# INVERTER.net
KiCad netlist of a schematic drawn in Altium Designer
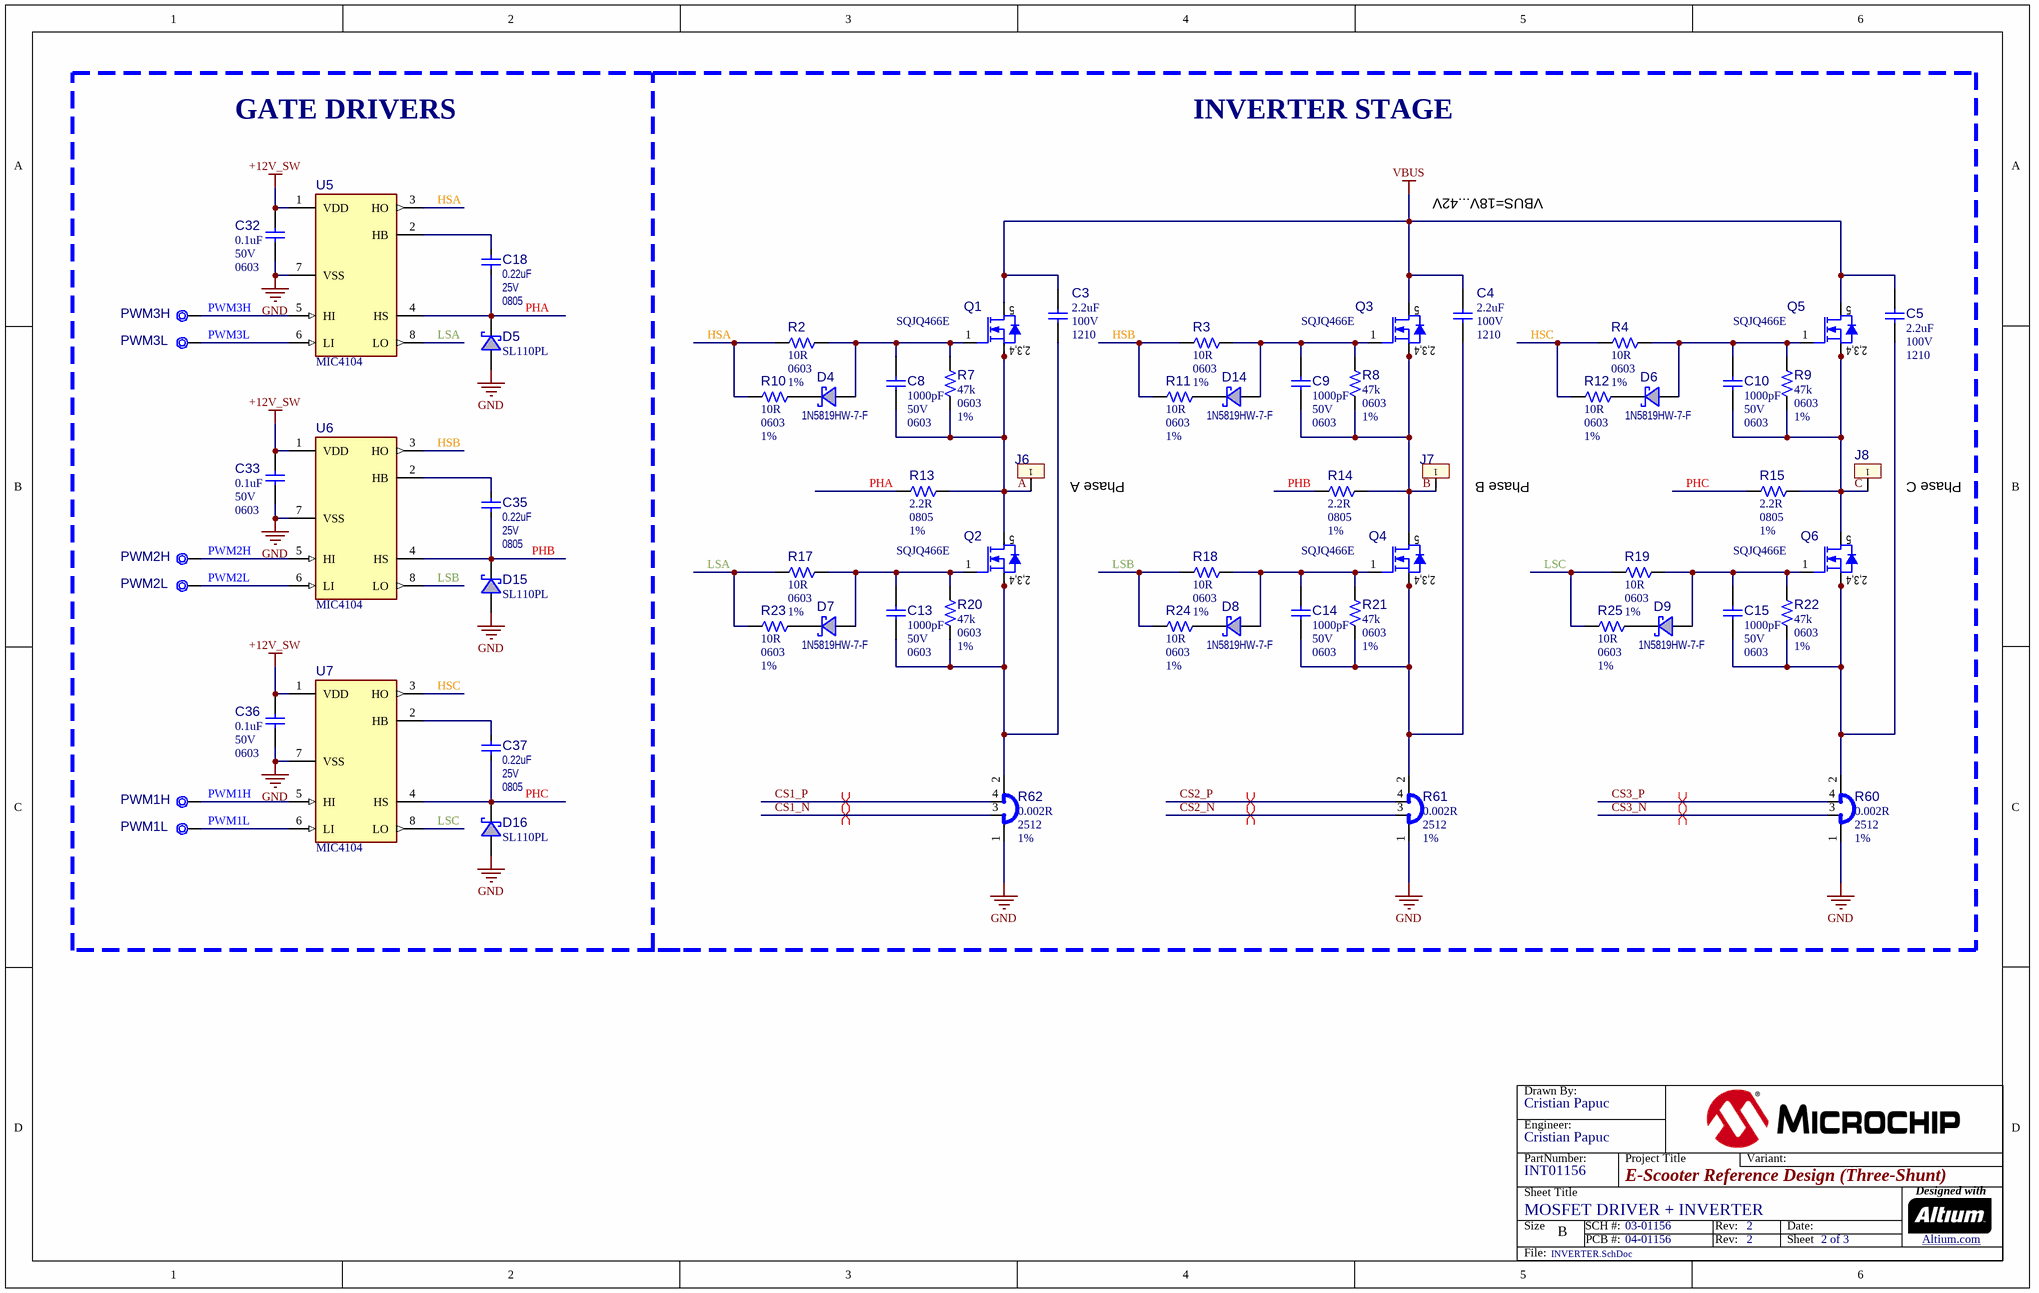
[diagram p0: INVERTER.SchDoc]

(export (version "E")
  (design (tool "Eeschema 10.0.6"))
  (components
    (comp (ref "C3")
      (value "2.2uF")
      (footprint "CAP_C_1210")
      (description "Capacitor")
      (fields
        (field (name "VOLTAGE") "100V")
        (field (name "PACKAGE") "1210")
        (field (name "TOLERANCE") "10%")
        (field (name "Comment") "Capacitor NP")
        (field (name "OWNER") "Mihai T(M91442)")
      )
      (libsource (lib "") (part "Capacitor NP_2"))
    )
    (comp (ref "C4")
      (value "2.2uF")
      (footprint "CAP_C_1210")
      (description "Capacitor")
      (fields
        (field (name "VOLTAGE") "100V")
        (field (name "PACKAGE") "1210")
        (field (name "TOLERANCE") "10%")
        (field (name "Comment") "Capacitor NP")
        (field (name "OWNER") "Mihai T(M91442)")
      )
      (libsource (lib "") (part "Capacitor NP_2"))
    )
    (comp (ref "C5")
      (value "2.2uF")
      (footprint "CAP_C_1210")
      (description "Capacitor")
      (fields
        (field (name "VOLTAGE") "100V")
        (field (name "PACKAGE") "1210")
        (field (name "TOLERANCE") "10%")
        (field (name "Comment") "Capacitor NP")
        (field (name "OWNER") "Mihai T(M91442)")
      )
      (libsource (lib "") (part "Capacitor NP_2"))
    )
    (comp (ref "C8")
      (value "1000pF")
      (footprint "CAP_C_0603")
      (fields
        (field (name "VOLTAGE") "50V")
        (field (name "PACKAGE") "0603")
        (field (name "TOLERANCE") "10%")
        (field (name "Comment") "Capacitor NP")
        (field (name "OWNER") "Gabor Bihari")
      )
      (libsource (lib "MCHP-CDB") (part "Capacitor NP"))
    )
    (comp (ref "C9")
      (value "1000pF")
      (footprint "CAP_C_0603")
      (fields
        (field (name "VOLTAGE") "50V")
        (field (name "PACKAGE") "0603")
        (field (name "TOLERANCE") "10%")
        (field (name "Comment") "Capacitor NP")
        (field (name "OWNER") "Gabor Bihari")
      )
      (libsource (lib "MCHP-CDB") (part "Capacitor NP"))
    )
    (comp (ref "C10")
      (value "1000pF")
      (footprint "CAP_C_0603")
      (fields
        (field (name "VOLTAGE") "50V")
        (field (name "PACKAGE") "0603")
        (field (name "TOLERANCE") "10%")
        (field (name "Comment") "Capacitor NP")
        (field (name "OWNER") "Gabor Bihari")
      )
      (libsource (lib "MCHP-CDB") (part "Capacitor NP"))
    )
    (comp (ref "C13")
      (value "1000pF")
      (footprint "CAP_C_0603")
      (fields
        (field (name "VOLTAGE") "50V")
        (field (name "PACKAGE") "0603")
        (field (name "TOLERANCE") "10%")
        (field (name "Comment") "Capacitor NP")
        (field (name "OWNER") "Gabor Bihari")
      )
      (libsource (lib "MCHP-CDB") (part "Capacitor NP"))
    )
    (comp (ref "C14")
      (value "1000pF")
      (footprint "CAP_C_0603")
      (fields
        (field (name "VOLTAGE") "50V")
        (field (name "PACKAGE") "0603")
        (field (name "TOLERANCE") "10%")
        (field (name "Comment") "Capacitor NP")
        (field (name "OWNER") "Gabor Bihari")
      )
      (libsource (lib "MCHP-CDB") (part "Capacitor NP"))
    )
    (comp (ref "C15")
      (value "1000pF")
      (footprint "CAP_C_0603")
      (fields
        (field (name "VOLTAGE") "50V")
        (field (name "PACKAGE") "0603")
        (field (name "TOLERANCE") "10%")
        (field (name "Comment") "Capacitor NP")
        (field (name "OWNER") "Gabor Bihari")
      )
      (libsource (lib "MCHP-CDB") (part "Capacitor NP"))
    )
    (comp (ref "C18")
      (value "0.22uF")
      (footprint "CAP_C_0805")
      (fields
        (field (name "VOLTAGE") "25V")
        (field (name "PACKAGE") "0805")
        (field (name "TOLERANCE") "10%")
        (field (name "Comment") "Capacitor NP")
      )
      (libsource (lib "") (part "Capacitor NP_1"))
    )
    (comp (ref "C32")
      (value "0.1uF")
      (footprint "CAP_C_0603")
      (description "Capacitor")
      (fields
        (field (name "VOLTAGE") "50V")
        (field (name "PACKAGE") "0603")
        (field (name "TOLERANCE") "10%")
        (field (name "Comment") "Capacitor NP")
        (field (name "OWNER") "Sam Charles")
      )
      (libsource (lib "MCHP-CDB") (part "Capacitor NP"))
    )
    (comp (ref "C33")
      (value "0.1uF")
      (footprint "CAP_C_0603")
      (description "Capacitor")
      (fields
        (field (name "VOLTAGE") "50V")
        (field (name "PACKAGE") "0603")
        (field (name "TOLERANCE") "10%")
        (field (name "Comment") "Capacitor NP")
        (field (name "OWNER") "Sam Charles")
      )
      (libsource (lib "MCHP-CDB") (part "Capacitor NP"))
    )
    (comp (ref "C35")
      (value "0.22uF")
      (footprint "CAP_C_0805")
      (fields
        (field (name "VOLTAGE") "25V")
        (field (name "PACKAGE") "0805")
        (field (name "TOLERANCE") "10%")
        (field (name "Comment") "Capacitor NP")
      )
      (libsource (lib "") (part "Capacitor NP_1"))
    )
    (comp (ref "C36")
      (value "0.1uF")
      (footprint "CAP_C_0603")
      (description "Capacitor")
      (fields
        (field (name "VOLTAGE") "50V")
        (field (name "PACKAGE") "0603")
        (field (name "TOLERANCE") "10%")
        (field (name "Comment") "Capacitor NP")
        (field (name "OWNER") "Sam Charles")
      )
      (libsource (lib "MCHP-CDB") (part "Capacitor NP"))
    )
    (comp (ref "C37")
      (value "0.22uF")
      (footprint "CAP_C_0805")
      (fields
        (field (name "VOLTAGE") "25V")
        (field (name "PACKAGE") "0805")
        (field (name "TOLERANCE") "10%")
        (field (name "Comment") "Capacitor NP")
      )
      (libsource (lib "") (part "Capacitor NP_1"))
    )
    (comp (ref "D4")
      (value "1N5819HW-7-F")
      (footprint "SOD-123")
      (description "DIO SCTKY RB160M-60TR 550mV 1A 60V SMD SOD-123F")
      (fields
        (field (name "POWER") "450mW")
        (field (name "Comment") "Diode Schottky")
        (field (name "OWNER") "Sorin Stanoaia")
      )
      (libsource (lib "MCHP-CDB") (part "Diode Schottky"))
    )
    (comp (ref "D5")
      (value "SL110PL")
      (footprint "SOD-123FL")
      (description "DIO SCTKY RB160M-60TR 550mV 1A 60V SMD SOD-123F")
      (fields (field (name "Comment") "Diode Schottky") (field (name "OWNER") "Tad Ahlvers"))
      (libsource (lib "MCHP-CDB") (part "Diode Schottky"))
    )
    (comp (ref "D6")
      (value "1N5819HW-7-F")
      (footprint "SOD-123")
      (description "DIO SCTKY RB160M-60TR 550mV 1A 60V SMD SOD-123F")
      (fields
        (field (name "POWER") "450mW")
        (field (name "Comment") "Diode Schottky")
        (field (name "OWNER") "Sorin Stanoaia")
      )
      (libsource (lib "MCHP-CDB") (part "Diode Schottky"))
    )
    (comp (ref "D7")
      (value "1N5819HW-7-F")
      (footprint "SOD-123")
      (description "DIO SCTKY RB160M-60TR 550mV 1A 60V SMD SOD-123F")
      (fields
        (field (name "POWER") "450mW")
        (field (name "Comment") "Diode Schottky")
        (field (name "OWNER") "Sorin Stanoaia")
      )
      (libsource (lib "MCHP-CDB") (part "Diode Schottky"))
    )
    (comp (ref "D8")
      (value "1N5819HW-7-F")
      (footprint "SOD-123")
      (description "DIO SCTKY RB160M-60TR 550mV 1A 60V SMD SOD-123F")
      (fields
        (field (name "POWER") "450mW")
        (field (name "Comment") "Diode Schottky")
        (field (name "OWNER") "Sorin Stanoaia")
      )
      (libsource (lib "MCHP-CDB") (part "Diode Schottky"))
    )
    (comp (ref "D9")
      (value "1N5819HW-7-F")
      (footprint "SOD-123")
      (description "DIO SCTKY RB160M-60TR 550mV 1A 60V SMD SOD-123F")
      (fields
        (field (name "POWER") "450mW")
        (field (name "Comment") "Diode Schottky")
        (field (name "OWNER") "Sorin Stanoaia")
      )
      (libsource (lib "MCHP-CDB") (part "Diode Schottky"))
    )
    (comp (ref "D14")
      (value "1N5819HW-7-F")
      (footprint "SOD-123")
      (description "DIO SCTKY RB160M-60TR 550mV 1A 60V SMD SOD-123F")
      (fields
        (field (name "POWER") "450mW")
        (field (name "Comment") "Diode Schottky")
        (field (name "OWNER") "Sorin Stanoaia")
      )
      (libsource (lib "MCHP-CDB") (part "Diode Schottky"))
    )
    (comp (ref "D15")
      (value "SL110PL")
      (footprint "SOD-123FL")
      (description "DIO SCTKY RB160M-60TR 550mV 1A 60V SMD SOD-123F")
      (fields (field (name "Comment") "Diode Schottky") (field (name "OWNER") "Tad Ahlvers"))
      (libsource (lib "MCHP-CDB") (part "Diode Schottky"))
    )
    (comp (ref "D16")
      (value "SL110PL")
      (footprint "SOD-123FL")
      (description "DIO SCTKY RB160M-60TR 550mV 1A 60V SMD SOD-123F")
      (fields (field (name "Comment") "Diode Schottky") (field (name "OWNER") "Tad Ahlvers"))
      (libsource (lib "MCHP-CDB") (part "Diode Schottky"))
    )
    (comp (ref "J6")
      (value "Header 1x1")
      (footprint "CON_M_1x1_5.08_QC_TAB_SPADE_0.250_V")
      (description "CON HDR-2.54 Male 1x1 Gold 5.97MH TH VERT")
      (fields (field (name "OWNER") "Octavian Stroe"))
      (libsource (lib "MCHP-CDB") (part "Header 1x1"))
    )
    (comp (ref "J7")
      (value "Header 1x1")
      (footprint "CON_M_1x1_5.08_QC_TAB_SPADE_0.250_V")
      (description "CON HDR-2.54 Male 1x1 Gold 5.97MH TH VERT")
      (fields (field (name "OWNER") "Octavian Stroe"))
      (libsource (lib "MCHP-CDB") (part "Header 1x1"))
    )
    (comp (ref "J8")
      (value "Header 1x1")
      (footprint "CON_M_1x1_5.08_QC_TAB_SPADE_0.250_V")
      (description "CON HDR-2.54 Male 1x1 Gold 5.97MH TH VERT")
      (fields (field (name "OWNER") "Octavian Stroe"))
      (libsource (lib "MCHP-CDB") (part "Header 1x1"))
    )
    (comp (ref "PWM1H")
      (value "Test Point No BOM")
      (footprint "TP_1.2x0.7")
      (description "Test Point")
      (fields (field (name "OWNER") "Bogdan P (M91398)"))
      (libsource (lib "MCHP-CDB") (part "Test Point No BOM"))
    )
    (comp (ref "PWM1L")
      (value "Test Point No BOM")
      (footprint "TP_1.2x0.7")
      (description "Test Point")
      (fields (field (name "OWNER") "Bogdan P (M91398)"))
      (libsource (lib "MCHP-CDB") (part "Test Point No BOM"))
    )
    (comp (ref "PWM2H")
      (value "Test Point No BOM")
      (footprint "TP_1.2x0.7")
      (description "Test Point")
      (fields (field (name "OWNER") "Bogdan P (M91398)"))
      (libsource (lib "MCHP-CDB") (part "Test Point No BOM"))
    )
    (comp (ref "PWM2L")
      (value "Test Point No BOM")
      (footprint "TP_1.2x0.7")
      (description "Test Point")
      (fields (field (name "OWNER") "Bogdan P (M91398)"))
      (libsource (lib "MCHP-CDB") (part "Test Point No BOM"))
    )
    (comp (ref "PWM3H")
      (value "Test Point No BOM")
      (footprint "TP_1.2x0.7")
      (description "Test Point")
      (fields (field (name "OWNER") "Bogdan P (M91398)"))
      (libsource (lib "MCHP-CDB") (part "Test Point No BOM"))
    )
    (comp (ref "PWM3L")
      (value "Test Point No BOM")
      (footprint "TP_1.2x0.7")
      (description "Test Point")
      (fields (field (name "OWNER") "Bogdan P (M91398)"))
      (libsource (lib "MCHP-CDB") (part "Test Point No BOM"))
    )
    (comp (ref "Q1")
      (value "SQJQ466E")
      (footprint "PPAK_SO-8L_8x8_ALTERNATE")
      (description "Transistor MOS")
      (fields
        (field (name "POWER") "150W")
        (field (name "VOLTAGE") "60V")
        (field (name "OWNER") "Octavian Stroe")
      )
      (libsource (lib "MCHP-CDB") (part "Transistor MOS-N GSSSD"))
    )
    (comp (ref "Q2")
      (value "SQJQ466E")
      (footprint "PPAK_SO-8L_8x8_ALTERNATE")
      (description "Transistor MOS")
      (fields
        (field (name "POWER") "150W")
        (field (name "VOLTAGE") "60V")
        (field (name "OWNER") "Octavian Stroe")
      )
      (libsource (lib "MCHP-CDB") (part "Transistor MOS-N GSSSD"))
    )
    (comp (ref "Q3")
      (value "SQJQ466E")
      (footprint "PPAK_SO-8L_8x8_ALTERNATE")
      (description "Transistor MOS")
      (fields
        (field (name "POWER") "150W")
        (field (name "VOLTAGE") "60V")
        (field (name "OWNER") "Octavian Stroe")
      )
      (libsource (lib "MCHP-CDB") (part "Transistor MOS-N GSSSD"))
    )
    (comp (ref "Q4")
      (value "SQJQ466E")
      (footprint "PPAK_SO-8L_8x8_ALTERNATE")
      (description "Transistor MOS")
      (fields
        (field (name "POWER") "150W")
        (field (name "VOLTAGE") "60V")
        (field (name "OWNER") "Octavian Stroe")
      )
      (libsource (lib "MCHP-CDB") (part "Transistor MOS-N GSSSD"))
    )
    (comp (ref "Q5")
      (value "SQJQ466E")
      (footprint "PPAK_SO-8L_8x8_ALTERNATE")
      (description "Transistor MOS")
      (fields
        (field (name "POWER") "150W")
        (field (name "VOLTAGE") "60V")
        (field (name "OWNER") "Octavian Stroe")
      )
      (libsource (lib "MCHP-CDB") (part "Transistor MOS-N GSSSD"))
    )
    (comp (ref "Q6")
      (value "SQJQ466E")
      (footprint "PPAK_SO-8L_8x8_ALTERNATE")
      (description "Transistor MOS")
      (fields
        (field (name "POWER") "150W")
        (field (name "VOLTAGE") "60V")
        (field (name "OWNER") "Octavian Stroe")
      )
      (libsource (lib "MCHP-CDB") (part "Transistor MOS-N GSSSD"))
    )
    (comp (ref "R2")
      (value "10R")
      (footprint "RES_C_0603")
      (description "Resistor")
      (fields
        (field (name "PACKAGE") "0603")
        (field (name "TOLERANCE") "1%")
        (field (name "VOLTAGE") "75V")
        (field (name "POWER") "1/10W")
      )
      (libsource (lib "MCHP-CDB") (part "Resistor"))
    )
    (comp (ref "R3")
      (value "10R")
      (footprint "RES_C_0603")
      (description "Resistor")
      (fields
        (field (name "PACKAGE") "0603")
        (field (name "TOLERANCE") "1%")
        (field (name "VOLTAGE") "75V")
        (field (name "POWER") "1/10W")
      )
      (libsource (lib "MCHP-CDB") (part "Resistor"))
    )
    (comp (ref "R4")
      (value "10R")
      (footprint "RES_C_0603")
      (description "Resistor")
      (fields
        (field (name "PACKAGE") "0603")
        (field (name "TOLERANCE") "1%")
        (field (name "VOLTAGE") "75V")
        (field (name "POWER") "1/10W")
      )
      (libsource (lib "MCHP-CDB") (part "Resistor"))
    )
    (comp (ref "R7")
      (value "47k")
      (footprint "RES_C_0603")
      (description "Resistor")
      (fields
        (field (name "PACKAGE") "0603")
        (field (name "TOLERANCE") "1%")
        (field (name "VOLTAGE") "75V")
        (field (name "POWER") "1/10W")
        (field (name "OWNER") "Adrian M (M91404)")
      )
      (libsource (lib "MCHP-CDB") (part "Resistor"))
    )
    (comp (ref "R8")
      (value "47k")
      (footprint "RES_C_0603")
      (description "Resistor")
      (fields
        (field (name "PACKAGE") "0603")
        (field (name "TOLERANCE") "1%")
        (field (name "VOLTAGE") "75V")
        (field (name "POWER") "1/10W")
        (field (name "OWNER") "Adrian M (M91404)")
      )
      (libsource (lib "MCHP-CDB") (part "Resistor"))
    )
    (comp (ref "R9")
      (value "47k")
      (footprint "RES_C_0603")
      (description "Resistor")
      (fields
        (field (name "PACKAGE") "0603")
        (field (name "TOLERANCE") "1%")
        (field (name "VOLTAGE") "75V")
        (field (name "POWER") "1/10W")
        (field (name "OWNER") "Adrian M (M91404)")
      )
      (libsource (lib "MCHP-CDB") (part "Resistor"))
    )
    (comp (ref "R10")
      (value "10R")
      (footprint "RES_C_0603")
      (description "Resistor")
      (fields
        (field (name "PACKAGE") "0603")
        (field (name "TOLERANCE") "1%")
        (field (name "VOLTAGE") "75V")
        (field (name "POWER") "1/10W")
      )
      (libsource (lib "MCHP-CDB") (part "Resistor"))
    )
    (comp (ref "R11")
      (value "10R")
      (footprint "RES_C_0603")
      (description "Resistor")
      (fields
        (field (name "PACKAGE") "0603")
        (field (name "TOLERANCE") "1%")
        (field (name "VOLTAGE") "75V")
        (field (name "POWER") "1/10W")
      )
      (libsource (lib "MCHP-CDB") (part "Resistor"))
    )
    (comp (ref "R12")
      (value "10R")
      (footprint "RES_C_0603")
      (description "Resistor")
      (fields
        (field (name "PACKAGE") "0603")
        (field (name "TOLERANCE") "1%")
        (field (name "VOLTAGE") "75V")
        (field (name "POWER") "1/10W")
      )
      (libsource (lib "MCHP-CDB") (part "Resistor"))
    )
    (comp (ref "R13")
      (value "2.2R")
      (footprint "RES_C_0805")
      (description "Resistor")
      (fields
        (field (name "PACKAGE") "0805")
        (field (name "TOLERANCE") "1%")
        (field (name "VOLTAGE") "150V")
        (field (name "POWER") "1/8W")
        (field (name "OWNER") "Cristian Papuc")
      )
      (libsource (lib "MCHP-CDB") (part "Resistor"))
    )
    (comp (ref "R14")
      (value "2.2R")
      (footprint "RES_C_0805")
      (description "Resistor")
      (fields
        (field (name "PACKAGE") "0805")
        (field (name "TOLERANCE") "1%")
        (field (name "VOLTAGE") "150V")
        (field (name "POWER") "1/8W")
        (field (name "OWNER") "Cristian Papuc")
      )
      (libsource (lib "MCHP-CDB") (part "Resistor"))
    )
    (comp (ref "R15")
      (value "2.2R")
      (footprint "RES_C_0805")
      (description "Resistor")
      (fields
        (field (name "PACKAGE") "0805")
        (field (name "TOLERANCE") "1%")
        (field (name "VOLTAGE") "150V")
        (field (name "POWER") "1/8W")
        (field (name "OWNER") "Cristian Papuc")
      )
      (libsource (lib "MCHP-CDB") (part "Resistor"))
    )
    (comp (ref "R17")
      (value "10R")
      (footprint "RES_C_0603")
      (description "Resistor")
      (fields
        (field (name "PACKAGE") "0603")
        (field (name "TOLERANCE") "1%")
        (field (name "VOLTAGE") "75V")
        (field (name "POWER") "1/10W")
      )
      (libsource (lib "MCHP-CDB") (part "Resistor"))
    )
    (comp (ref "R18")
      (value "10R")
      (footprint "RES_C_0603")
      (description "Resistor")
      (fields
        (field (name "PACKAGE") "0603")
        (field (name "TOLERANCE") "1%")
        (field (name "VOLTAGE") "75V")
        (field (name "POWER") "1/10W")
      )
      (libsource (lib "MCHP-CDB") (part "Resistor"))
    )
    (comp (ref "R19")
      (value "10R")
      (footprint "RES_C_0603")
      (description "Resistor")
      (fields
        (field (name "PACKAGE") "0603")
        (field (name "TOLERANCE") "1%")
        (field (name "VOLTAGE") "75V")
        (field (name "POWER") "1/10W")
      )
      (libsource (lib "MCHP-CDB") (part "Resistor"))
    )
    (comp (ref "R20")
      (value "47k")
      (footprint "RES_C_0603")
      (description "Resistor")
      (fields
        (field (name "PACKAGE") "0603")
        (field (name "TOLERANCE") "1%")
        (field (name "VOLTAGE") "75V")
        (field (name "POWER") "1/10W")
        (field (name "OWNER") "Adrian M (M91404)")
      )
      (libsource (lib "MCHP-CDB") (part "Resistor"))
    )
    (comp (ref "R21")
      (value "47k")
      (footprint "RES_C_0603")
      (description "Resistor")
      (fields
        (field (name "PACKAGE") "0603")
        (field (name "TOLERANCE") "1%")
        (field (name "VOLTAGE") "75V")
        (field (name "POWER") "1/10W")
        (field (name "OWNER") "Adrian M (M91404)")
      )
      (libsource (lib "MCHP-CDB") (part "Resistor"))
    )
    (comp (ref "R22")
      (value "47k")
      (footprint "RES_C_0603")
      (description "Resistor")
      (fields
        (field (name "PACKAGE") "0603")
        (field (name "TOLERANCE") "1%")
        (field (name "VOLTAGE") "75V")
        (field (name "POWER") "1/10W")
        (field (name "OWNER") "Adrian M (M91404)")
      )
      (libsource (lib "MCHP-CDB") (part "Resistor"))
    )
    (comp (ref "R23")
      (value "10R")
      (footprint "RES_C_0603")
      (description "Resistor")
      (fields
        (field (name "PACKAGE") "0603")
        (field (name "TOLERANCE") "1%")
        (field (name "VOLTAGE") "75V")
        (field (name "POWER") "1/10W")
      )
      (libsource (lib "MCHP-CDB") (part "Resistor"))
    )
    (comp (ref "R24")
      (value "10R")
      (footprint "RES_C_0603")
      (description "Resistor")
      (fields
        (field (name "PACKAGE") "0603")
        (field (name "TOLERANCE") "1%")
        (field (name "VOLTAGE") "75V")
        (field (name "POWER") "1/10W")
      )
      (libsource (lib "MCHP-CDB") (part "Resistor"))
    )
    (comp (ref "R25")
      (value "10R")
      (footprint "RES_C_0603")
      (description "Resistor")
      (fields
        (field (name "PACKAGE") "0603")
        (field (name "TOLERANCE") "1%")
        (field (name "VOLTAGE") "75V")
        (field (name "POWER") "1/10W")
      )
      (libsource (lib "MCHP-CDB") (part "Resistor"))
    )
    (comp (ref "R60")
      (value "0.002R")
      (footprint "RES_C_2512_SHUNT_Metal")
      (description "Shunt")
      (fields
        (field (name "PACKAGE") "2512")
        (field (name "TOLERANCE") "1%")
        (field (name "POWER") "5W")
        (field (name "Comment") "Shunt 4 Pin")
        (field (name "OWNER") "Octavian Stroe")
      )
      (libsource (lib "MCHP-CDB") (part "Shunt 4 Pin"))
    )
    (comp (ref "R61")
      (value "0.002R")
      (footprint "RES_C_2512_SHUNT_Metal")
      (description "Shunt")
      (fields
        (field (name "PACKAGE") "2512")
        (field (name "TOLERANCE") "1%")
        (field (name "POWER") "5W")
        (field (name "Comment") "Shunt 4 Pin")
        (field (name "OWNER") "Octavian Stroe")
      )
      (libsource (lib "MCHP-CDB") (part "Shunt 4 Pin"))
    )
    (comp (ref "R62")
      (value "0.002R")
      (footprint "RES_C_2512_SHUNT_Metal")
      (description "Shunt")
      (fields
        (field (name "PACKAGE") "2512")
        (field (name "TOLERANCE") "1%")
        (field (name "POWER") "5W")
        (field (name "Comment") "Shunt 4 Pin")
        (field (name "OWNER") "Octavian Stroe")
      )
      (libsource (lib "MCHP-CDB") (part "Shunt 4 Pin"))
    )
    (comp (ref "U5")
      (value "MIC4104")
      (footprint "SOIC-8")
      (description "MOSFET DRIVER")
      (fields (field (name "Comment") "MIC4104 SOIC-8") (field (name "OWNER") "Ed Kennedy"))
      (libsource (lib "MCHP-CDB") (part "MIC4104 SOIC-8"))
    )
    (comp (ref "U6")
      (value "MIC4104")
      (footprint "SOIC-8")
      (description "MOSFET DRIVER")
      (fields (field (name "Comment") "MIC4104 SOIC-8") (field (name "OWNER") "Ed Kennedy"))
      (libsource (lib "MCHP-CDB") (part "MIC4104 SOIC-8"))
    )
    (comp (ref "U7")
      (value "MIC4104")
      (footprint "SOIC-8")
      (description "MOSFET DRIVER")
      (fields (field (name "Comment") "MIC4104 SOIC-8") (field (name "OWNER") "Ed Kennedy"))
      (libsource (lib "MCHP-CDB") (part "MIC4104 SOIC-8"))
    )
  )
  (nets
    (net (code "1") (name "+12V_SW") (class "Default")
      (node (ref "C32") (pin "2") (pinfunction "2_2") (pintype "passive"))
      (node (ref "C33") (pin "2") (pinfunction "2_2") (pintype "passive"))
      (node (ref "C36") (pin "2") (pinfunction "2_2") (pintype "passive"))
      (node (ref "U5") (pin "1") (pinfunction "VDD_1") (pintype "power_in"))
      (node (ref "U6") (pin "1") (pinfunction "VDD_1") (pintype "power_in"))
      (node (ref "U7") (pin "1") (pinfunction "VDD_1") (pintype "power_in"))
    )
    (net (code "2") (name "/A") (class "Default")
      (node (ref "C8") (pin "1") (pinfunction "1_1") (pintype "passive"))
      (node (ref "J6") (pin "1") (pinfunction "1_1") (pintype "passive"))
      (node (ref "Q1") (pin "2") (pinfunction "S_2") (pintype "passive"))
      (node (ref "Q1") (pin "3") (pinfunction "S_3") (pintype "passive"))
      (node (ref "Q1") (pin "4") (pinfunction "S_4") (pintype "passive"))
      (node (ref "Q2") (pin "5") (pinfunction "D_5") (pintype "passive"))
      (node (ref "R13") (pin "2") (pinfunction "2_2") (pintype "passive"))
      (node (ref "R7") (pin "1") (pinfunction "1_1") (pintype "passive"))
    )
    (net (code "3") (name "/B") (class "Default")
      (node (ref "C9") (pin "1") (pinfunction "1_1") (pintype "passive"))
      (node (ref "J7") (pin "1") (pinfunction "1_1") (pintype "passive"))
      (node (ref "Q3") (pin "2") (pinfunction "S_2") (pintype "passive"))
      (node (ref "Q3") (pin "3") (pinfunction "S_3") (pintype "passive"))
      (node (ref "Q3") (pin "4") (pinfunction "S_4") (pintype "passive"))
      (node (ref "Q4") (pin "5") (pinfunction "D_5") (pintype "passive"))
      (node (ref "R14") (pin "2") (pinfunction "2_2") (pintype "passive"))
      (node (ref "R8") (pin "1") (pinfunction "1_1") (pintype "passive"))
    )
    (net (code "4") (name "/C") (class "Default")
      (node (ref "C10") (pin "1") (pinfunction "1_1") (pintype "passive"))
      (node (ref "J8") (pin "1") (pinfunction "1_1") (pintype "passive"))
      (node (ref "Q5") (pin "2") (pinfunction "S_2") (pintype "passive"))
      (node (ref "Q5") (pin "3") (pinfunction "S_3") (pintype "passive"))
      (node (ref "Q5") (pin "4") (pinfunction "S_4") (pintype "passive"))
      (node (ref "Q6") (pin "5") (pinfunction "D_5") (pintype "passive"))
      (node (ref "R15") (pin "2") (pinfunction "2_2") (pintype "passive"))
      (node (ref "R9") (pin "1") (pinfunction "1_1") (pintype "passive"))
    )
    (net (code "5") (name "/CS1_N") (class "Default")
      (node (ref "R62") (pin "3") (pinfunction "3_3") (pintype "passive"))
    )
    (net (code "6") (name "/CS1_P") (class "Default")
      (node (ref "R62") (pin "4") (pinfunction "4_4") (pintype "passive"))
    )
    (net (code "7") (name "/CS2_N") (class "Default")
      (node (ref "R61") (pin "3") (pinfunction "3_3") (pintype "passive"))
    )
    (net (code "8") (name "/CS2_P") (class "Default")
      (node (ref "R61") (pin "4") (pinfunction "4_4") (pintype "passive"))
    )
    (net (code "9") (name "/CS3_N") (class "Default")
      (node (ref "R60") (pin "3") (pinfunction "3_3") (pintype "passive"))
    )
    (net (code "10") (name "/CS3_P") (class "Default")
      (node (ref "R60") (pin "4") (pinfunction "4_4") (pintype "passive"))
    )
    (net (code "11") (name "/HSA") (class "Default")
      (node (ref "R10") (pin "1") (pinfunction "1_1") (pintype "passive"))
      (node (ref "R2") (pin "1") (pinfunction "1_1") (pintype "passive"))
      (node (ref "U5") (pin "3") (pinfunction "HO_3") (pintype "output"))
    )
    (net (code "12") (name "/HSB") (class "Default")
      (node (ref "R11") (pin "1") (pinfunction "1_1") (pintype "passive"))
      (node (ref "R3") (pin "1") (pinfunction "1_1") (pintype "passive"))
      (node (ref "U6") (pin "3") (pinfunction "HO_3") (pintype "output"))
    )
    (net (code "13") (name "/HSC") (class "Default")
      (node (ref "R12") (pin "1") (pinfunction "1_1") (pintype "passive"))
      (node (ref "R4") (pin "1") (pinfunction "1_1") (pintype "passive"))
      (node (ref "U7") (pin "3") (pinfunction "HO_3") (pintype "output"))
    )
    (net (code "14") (name "/LSA") (class "Default")
      (node (ref "R17") (pin "1") (pinfunction "1_1") (pintype "passive"))
      (node (ref "R23") (pin "1") (pinfunction "1_1") (pintype "passive"))
      (node (ref "U5") (pin "8") (pinfunction "LO_8") (pintype "output"))
    )
    (net (code "15") (name "/LSB") (class "Default")
      (node (ref "R18") (pin "1") (pinfunction "1_1") (pintype "passive"))
      (node (ref "R24") (pin "1") (pinfunction "1_1") (pintype "passive"))
      (node (ref "U6") (pin "8") (pinfunction "LO_8") (pintype "output"))
    )
    (net (code "16") (name "/LSC") (class "Default")
      (node (ref "R19") (pin "1") (pinfunction "1_1") (pintype "passive"))
      (node (ref "R25") (pin "1") (pinfunction "1_1") (pintype "passive"))
      (node (ref "U7") (pin "8") (pinfunction "LO_8") (pintype "output"))
    )
    (net (code "17") (name "/PHA") (class "Default")
      (node (ref "C18") (pin "1") (pinfunction "1_1") (pintype "passive"))
      (node (ref "D5") (pin "2") (pinfunction "K_2") (pintype "passive"))
      (node (ref "R13") (pin "1") (pinfunction "1_1") (pintype "passive"))
      (node (ref "U5") (pin "4") (pinfunction "HS_4") (pintype "passive"))
    )
    (net (code "18") (name "/PHB") (class "Default")
      (node (ref "C35") (pin "1") (pinfunction "1_1") (pintype "passive"))
      (node (ref "D15") (pin "2") (pinfunction "K_2") (pintype "passive"))
      (node (ref "R14") (pin "1") (pinfunction "1_1") (pintype "passive"))
      (node (ref "U6") (pin "4") (pinfunction "HS_4") (pintype "passive"))
    )
    (net (code "19") (name "/PHC") (class "Default")
      (node (ref "C37") (pin "1") (pinfunction "1_1") (pintype "passive"))
      (node (ref "D16") (pin "2") (pinfunction "K_2") (pintype "passive"))
      (node (ref "R15") (pin "1") (pinfunction "1_1") (pintype "passive"))
      (node (ref "U7") (pin "4") (pinfunction "HS_4") (pintype "passive"))
    )
    (net (code "20") (name "/PWM1H") (class "Default")
      (node (ref "PWM1H") (pin "1") (pinfunction "1_1") (pintype "passive"))
      (node (ref "U7") (pin "5") (pinfunction "HI_5") (pintype "input"))
    )
    (net (code "21") (name "/PWM1L") (class "Default")
      (node (ref "PWM1L") (pin "1") (pinfunction "1_1") (pintype "passive"))
      (node (ref "U7") (pin "6") (pinfunction "LI_6") (pintype "input"))
    )
    (net (code "22") (name "/PWM2H") (class "Default")
      (node (ref "PWM2H") (pin "1") (pinfunction "1_1") (pintype "passive"))
      (node (ref "U6") (pin "5") (pinfunction "HI_5") (pintype "input"))
    )
    (net (code "23") (name "/PWM2L") (class "Default")
      (node (ref "PWM2L") (pin "1") (pinfunction "1_1") (pintype "passive"))
      (node (ref "U6") (pin "6") (pinfunction "LI_6") (pintype "input"))
    )
    (net (code "24") (name "/PWM3H") (class "Default")
      (node (ref "PWM3H") (pin "1") (pinfunction "1_1") (pintype "passive"))
      (node (ref "U5") (pin "5") (pinfunction "HI_5") (pintype "input"))
    )
    (net (code "25") (name "/PWM3L") (class "Default")
      (node (ref "PWM3L") (pin "1") (pinfunction "1_1") (pintype "passive"))
      (node (ref "U5") (pin "6") (pinfunction "LI_6") (pintype "input"))
    )
    (net (code "26") (name "GND") (class "Default")
      (node (ref "C32") (pin "1") (pinfunction "1_1") (pintype "passive"))
      (node (ref "C33") (pin "1") (pinfunction "1_1") (pintype "passive"))
      (node (ref "C36") (pin "1") (pinfunction "1_1") (pintype "passive"))
      (node (ref "D15") (pin "1") (pinfunction "A_1") (pintype "passive"))
      (node (ref "D16") (pin "1") (pinfunction "A_1") (pintype "passive"))
      (node (ref "D5") (pin "1") (pinfunction "A_1") (pintype "passive"))
      (node (ref "R60") (pin "1") (pinfunction "1_1") (pintype "passive"))
      (node (ref "R61") (pin "1") (pinfunction "1_1") (pintype "passive"))
      (node (ref "R62") (pin "1") (pinfunction "1_1") (pintype "passive"))
      (node (ref "U5") (pin "7") (pinfunction "VSS_7") (pintype "power_in"))
      (node (ref "U6") (pin "7") (pinfunction "VSS_7") (pintype "power_in"))
      (node (ref "U7") (pin "7") (pinfunction "VSS_7") (pintype "power_in"))
    )
    (net (code "27") (name "Net-(C13-Pad1)") (class "Default")
      (node (ref "C13") (pin "1") (pinfunction "1_1") (pintype "passive"))
      (node (ref "C3") (pin "1") (pinfunction "1_1") (pintype "passive"))
      (node (ref "Q2") (pin "2") (pinfunction "S_2") (pintype "passive"))
      (node (ref "Q2") (pin "3") (pinfunction "S_3") (pintype "passive"))
      (node (ref "Q2") (pin "4") (pinfunction "S_4") (pintype "passive"))
      (node (ref "R20") (pin "1") (pinfunction "1_1") (pintype "passive"))
      (node (ref "R62") (pin "2") (pinfunction "2_2") (pintype "passive"))
    )
    (net (code "28") (name "Net-(C14-Pad1)") (class "Default")
      (node (ref "C14") (pin "1") (pinfunction "1_1") (pintype "passive"))
      (node (ref "C4") (pin "1") (pinfunction "1_1") (pintype "passive"))
      (node (ref "Q4") (pin "2") (pinfunction "S_2") (pintype "passive"))
      (node (ref "Q4") (pin "3") (pinfunction "S_3") (pintype "passive"))
      (node (ref "Q4") (pin "4") (pinfunction "S_4") (pintype "passive"))
      (node (ref "R21") (pin "1") (pinfunction "1_1") (pintype "passive"))
      (node (ref "R61") (pin "2") (pinfunction "2_2") (pintype "passive"))
    )
    (net (code "29") (name "Net-(C15-Pad1)") (class "Default")
      (node (ref "C15") (pin "1") (pinfunction "1_1") (pintype "passive"))
      (node (ref "C5") (pin "1") (pinfunction "1_1") (pintype "passive"))
      (node (ref "Q6") (pin "2") (pinfunction "S_2") (pintype "passive"))
      (node (ref "Q6") (pin "3") (pinfunction "S_3") (pintype "passive"))
      (node (ref "Q6") (pin "4") (pinfunction "S_4") (pintype "passive"))
      (node (ref "R22") (pin "1") (pinfunction "1_1") (pintype "passive"))
      (node (ref "R60") (pin "2") (pinfunction "2_2") (pintype "passive"))
    )
    (net (code "30") (name "Net-(D4-A)") (class "Default")
      (node (ref "C8") (pin "2") (pinfunction "2_2") (pintype "passive"))
      (node (ref "D4") (pin "1") (pinfunction "A_1") (pintype "passive"))
      (node (ref "Q1") (pin "1") (pinfunction "G_1") (pintype "passive"))
      (node (ref "R2") (pin "2") (pinfunction "2_2") (pintype "passive"))
      (node (ref "R7") (pin "2") (pinfunction "2_2") (pintype "passive"))
    )
    (net (code "31") (name "Net-(D4-K)") (class "Default")
      (node (ref "D4") (pin "2") (pinfunction "K_2") (pintype "passive"))
      (node (ref "R10") (pin "2") (pinfunction "2_2") (pintype "passive"))
    )
    (net (code "32") (name "Net-(D6-A)") (class "Default")
      (node (ref "C10") (pin "2") (pinfunction "2_2") (pintype "passive"))
      (node (ref "D6") (pin "1") (pinfunction "A_1") (pintype "passive"))
      (node (ref "Q5") (pin "1") (pinfunction "G_1") (pintype "passive"))
      (node (ref "R4") (pin "2") (pinfunction "2_2") (pintype "passive"))
      (node (ref "R9") (pin "2") (pinfunction "2_2") (pintype "passive"))
    )
    (net (code "33") (name "Net-(D6-K)") (class "Default")
      (node (ref "D6") (pin "2") (pinfunction "K_2") (pintype "passive"))
      (node (ref "R12") (pin "2") (pinfunction "2_2") (pintype "passive"))
    )
    (net (code "34") (name "Net-(D7-A)") (class "Default")
      (node (ref "C13") (pin "2") (pinfunction "2_2") (pintype "passive"))
      (node (ref "D7") (pin "1") (pinfunction "A_1") (pintype "passive"))
      (node (ref "Q2") (pin "1") (pinfunction "G_1") (pintype "passive"))
      (node (ref "R17") (pin "2") (pinfunction "2_2") (pintype "passive"))
      (node (ref "R20") (pin "2") (pinfunction "2_2") (pintype "passive"))
    )
    (net (code "35") (name "Net-(D7-K)") (class "Default")
      (node (ref "D7") (pin "2") (pinfunction "K_2") (pintype "passive"))
      (node (ref "R23") (pin "2") (pinfunction "2_2") (pintype "passive"))
    )
    (net (code "36") (name "Net-(D8-A)") (class "Default")
      (node (ref "C14") (pin "2") (pinfunction "2_2") (pintype "passive"))
      (node (ref "D8") (pin "1") (pinfunction "A_1") (pintype "passive"))
      (node (ref "Q4") (pin "1") (pinfunction "G_1") (pintype "passive"))
      (node (ref "R18") (pin "2") (pinfunction "2_2") (pintype "passive"))
      (node (ref "R21") (pin "2") (pinfunction "2_2") (pintype "passive"))
    )
    (net (code "37") (name "Net-(D8-K)") (class "Default")
      (node (ref "D8") (pin "2") (pinfunction "K_2") (pintype "passive"))
      (node (ref "R24") (pin "2") (pinfunction "2_2") (pintype "passive"))
    )
    (net (code "38") (name "Net-(D9-A)") (class "Default")
      (node (ref "C15") (pin "2") (pinfunction "2_2") (pintype "passive"))
      (node (ref "D9") (pin "1") (pinfunction "A_1") (pintype "passive"))
      (node (ref "Q6") (pin "1") (pinfunction "G_1") (pintype "passive"))
      (node (ref "R19") (pin "2") (pinfunction "2_2") (pintype "passive"))
      (node (ref "R22") (pin "2") (pinfunction "2_2") (pintype "passive"))
    )
    (net (code "39") (name "Net-(D9-K)") (class "Default")
      (node (ref "D9") (pin "2") (pinfunction "K_2") (pintype "passive"))
      (node (ref "R25") (pin "2") (pinfunction "2_2") (pintype "passive"))
    )
    (net (code "40") (name "Net-(D14-A)") (class "Default")
      (node (ref "C9") (pin "2") (pinfunction "2_2") (pintype "passive"))
      (node (ref "D14") (pin "1") (pinfunction "A_1") (pintype "passive"))
      (node (ref "Q3") (pin "1") (pinfunction "G_1") (pintype "passive"))
      (node (ref "R3") (pin "2") (pinfunction "2_2") (pintype "passive"))
      (node (ref "R8") (pin "2") (pinfunction "2_2") (pintype "passive"))
    )
    (net (code "41") (name "Net-(D14-K)") (class "Default")
      (node (ref "D14") (pin "2") (pinfunction "K_2") (pintype "passive"))
      (node (ref "R11") (pin "2") (pinfunction "2_2") (pintype "passive"))
    )
    (net (code "42") (name "Net-(U5-HB)") (class "Default")
      (node (ref "C18") (pin "2") (pinfunction "2_2") (pintype "passive"))
      (node (ref "U5") (pin "2") (pinfunction "HB_2") (pintype "passive"))
    )
    (net (code "43") (name "Net-(U6-HB)") (class "Default")
      (node (ref "C35") (pin "2") (pinfunction "2_2") (pintype "passive"))
      (node (ref "U6") (pin "2") (pinfunction "HB_2") (pintype "passive"))
    )
    (net (code "44") (name "Net-(U7-HB)") (class "Default")
      (node (ref "C37") (pin "2") (pinfunction "2_2") (pintype "passive"))
      (node (ref "U7") (pin "2") (pinfunction "HB_2") (pintype "passive"))
    )
    (net (code "45") (name "VBUS") (class "Default")
      (node (ref "C3") (pin "2") (pinfunction "2_2") (pintype "passive"))
      (node (ref "C4") (pin "2") (pinfunction "2_2") (pintype "passive"))
      (node (ref "C5") (pin "2") (pinfunction "2_2") (pintype "passive"))
      (node (ref "Q1") (pin "5") (pinfunction "D_5") (pintype "passive"))
      (node (ref "Q3") (pin "5") (pinfunction "D_5") (pintype "passive"))
      (node (ref "Q5") (pin "5") (pinfunction "D_5") (pintype "passive"))
    )
  )
)
